# EthernetPhy.net
KiCad netlist of a schematic drawn in EAGLE
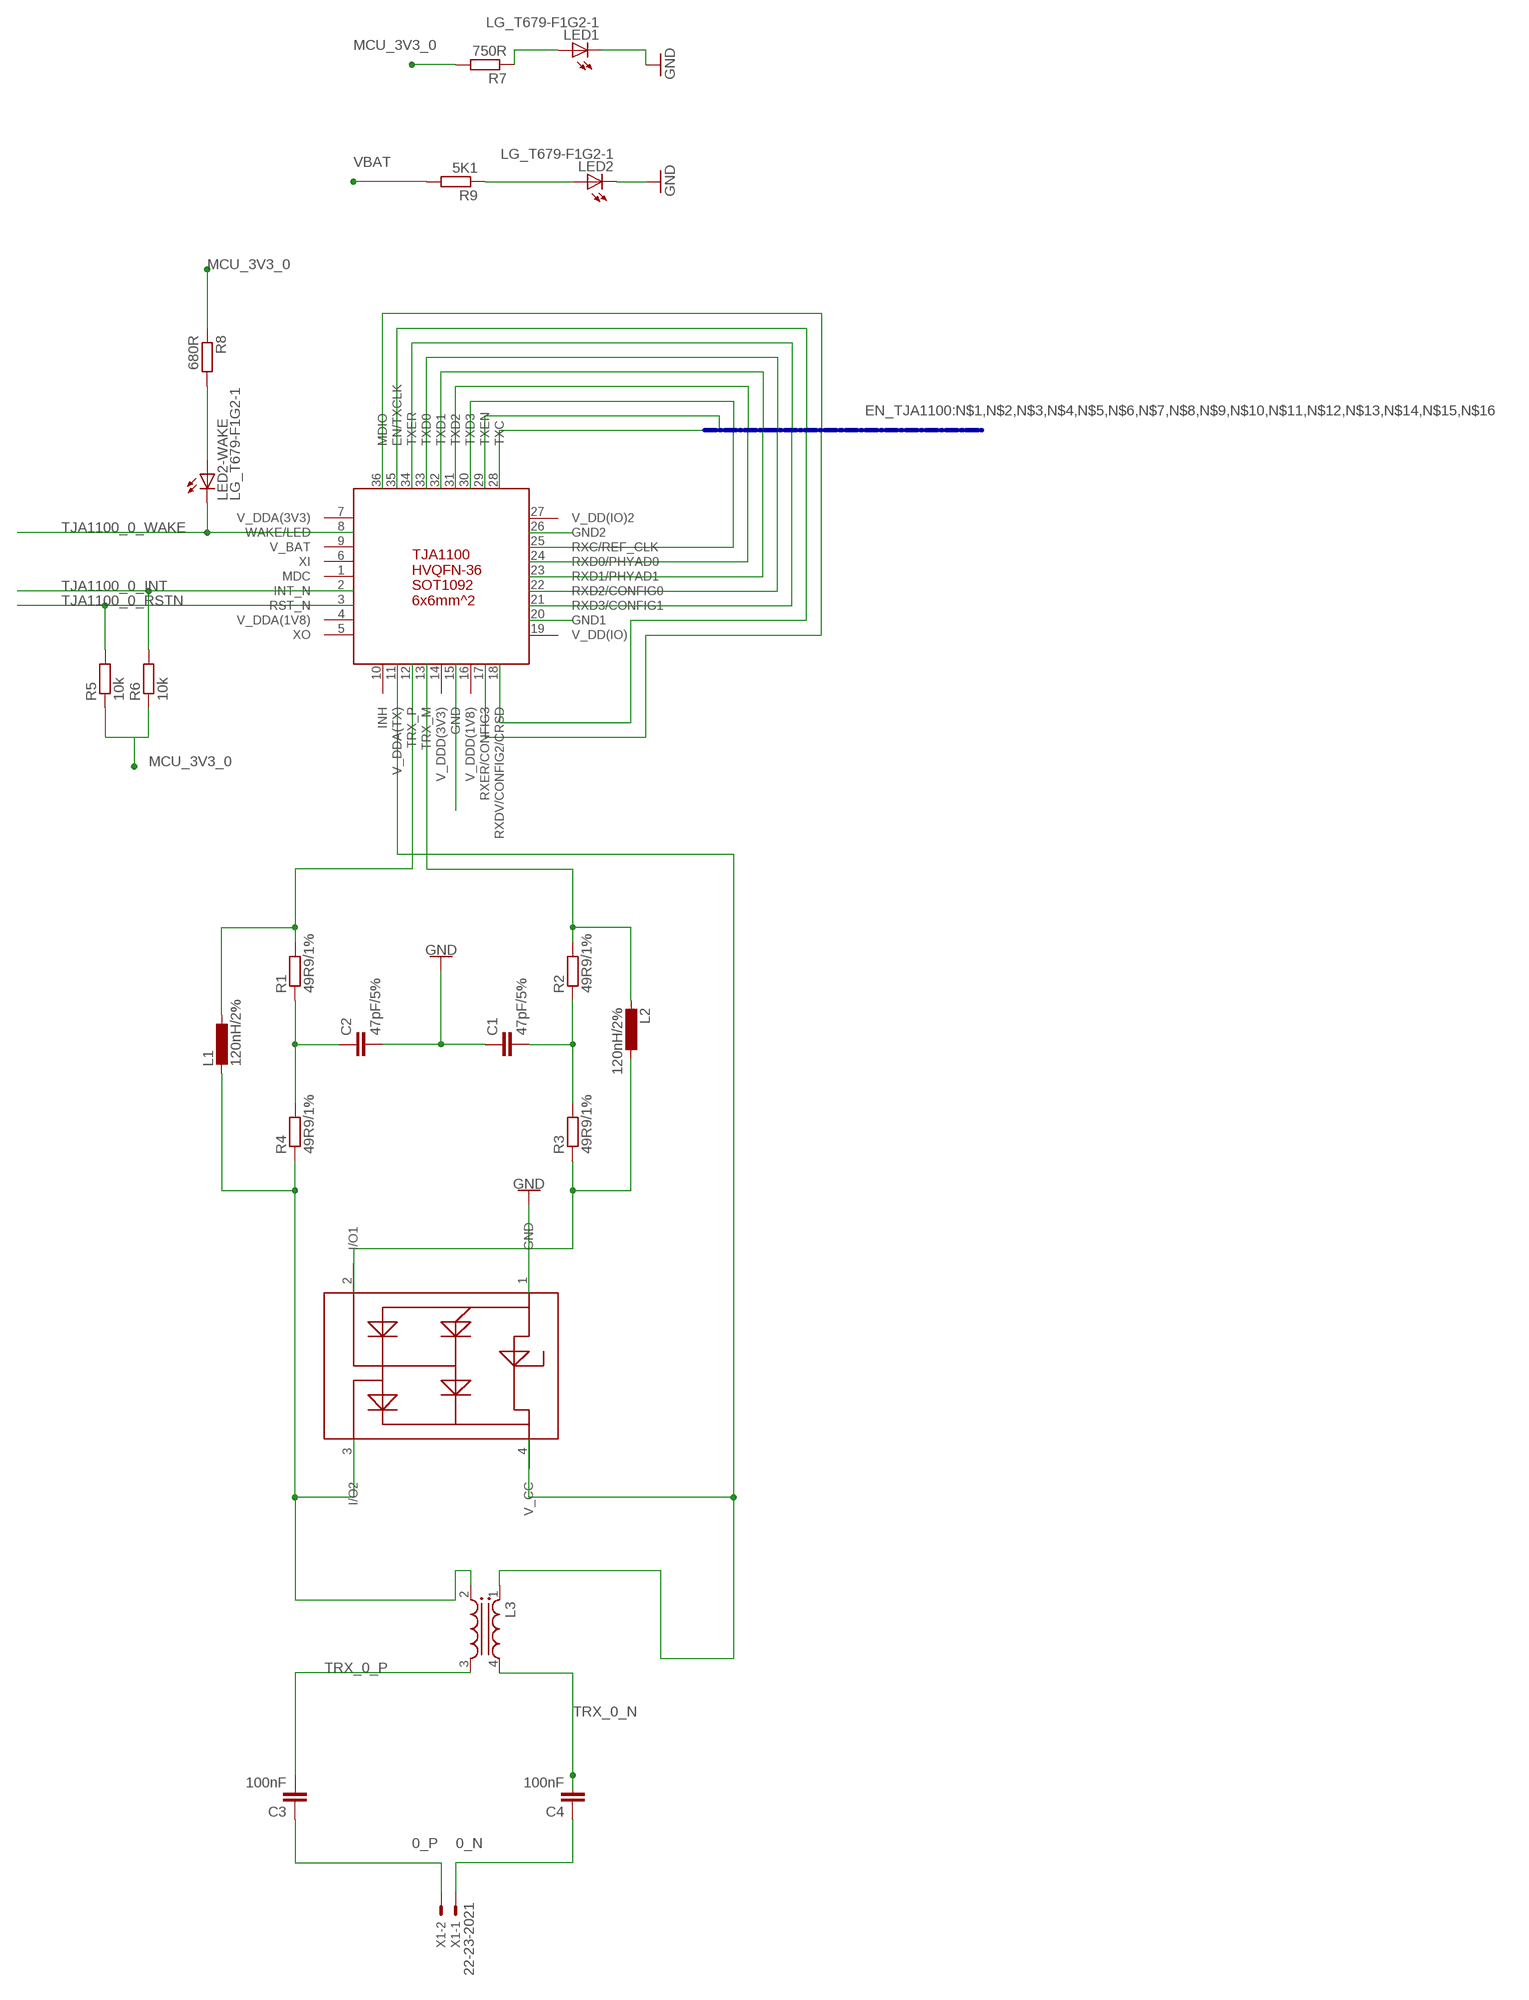
[diagram p0: schematic, sheet 1]

(export (version "E")
  (design (tool "Eeschema 10.0.6"))
  (components
    (comp (ref "C1")
      (value "47pF/5%")
      (footprint "eagle-import:C0402K")
      (libsource (lib "eagle-import") (part "C-EUC0402K"))
    )
    (comp (ref "C2")
      (value "47pF/5%")
      (footprint "eagle-import:C0402K")
      (libsource (lib "eagle-import") (part "C-EUC0402K"))
    )
    (comp (ref "C3")
      (value "100nF")
      (footprint "eagle-import:C0402K")
      (libsource (lib "eagle-import") (part "C-EUC0402K"))
    )
    (comp (ref "C4")
      (value "100nF")
      (footprint "eagle-import:C0402K")
      (libsource (lib "eagle-import") (part "C-EUC0402K"))
    )
    (comp (ref "L1")
      (value "120nH/2%")
      (footprint "eagle-import:L0201")
      (libsource (lib "eagle-import") (part "L-EUL0201"))
    )
    (comp (ref "L2")
      (value "120nH/2%")
      (footprint "eagle-import:L0201")
      (libsource (lib "eagle-import") (part "L-EUL0201"))
    )
    (comp (ref "L3")
      (value "WE-SL2_744224")
      (footprint "eagle-import:WE-SL2")
      (libsource (lib "eagle-import") (part "WE-SL2_744224"))
    )
    (comp (ref "LED1")
      (value "LG_T679-F1G2-1")
      (footprint "eagle-import:PLCC2")
      (libsource (lib "eagle-import") (part "_T679-?-1F1G2LG"))
    )
    (comp (ref "LED2")
      (value "LG_T679-F1G2-1")
      (footprint "eagle-import:PLCC2")
      (libsource (lib "eagle-import") (part "_T679-?-1F1G2LG"))
    )
    (comp (ref "LED2-WAKE")
      (value "LG_T679-F1G2-1")
      (footprint "eagle-import:PLCC2")
      (libsource (lib "eagle-import") (part "_T679-?-1F1G2LG"))
    )
    (comp (ref "R1")
      (value "49R9/1%")
      (footprint "eagle-import:MINI_MELF-0207R")
      (libsource (lib "eagle-import") (part "R-EU_MELF0207R"))
    )
    (comp (ref "R2")
      (value "49R9/1%")
      (footprint "eagle-import:MINI_MELF-0207R")
      (libsource (lib "eagle-import") (part "R-EU_MELF0207R"))
    )
    (comp (ref "R3")
      (value "49R9/1%")
      (footprint "eagle-import:MINI_MELF-0207R")
      (libsource (lib "eagle-import") (part "R-EU_MELF0207R"))
    )
    (comp (ref "R4")
      (value "49R9/1%")
      (footprint "eagle-import:MINI_MELF-0207R")
      (libsource (lib "eagle-import") (part "R-EU_MELF0207R"))
    )
    (comp (ref "R5")
      (value "10k")
      (footprint "eagle-import:R01005")
      (libsource (lib "eagle-import") (part "R-EU_01005"))
    )
    (comp (ref "R6")
      (value "10k")
      (footprint "eagle-import:R01005")
      (libsource (lib "eagle-import") (part "R-EU_01005"))
    )
    (comp (ref "R7")
      (value "750R")
      (footprint "eagle-import:R01005")
      (libsource (lib "eagle-import") (part "R-EU_01005"))
    )
    (comp (ref "R8")
      (value "680R")
      (footprint "eagle-import:R01005")
      (libsource (lib "eagle-import") (part "R-EU_01005"))
    )
    (comp (ref "R9")
      (value "5K1")
      (footprint "eagle-import:R01005")
      (libsource (lib "eagle-import") (part "R-EU_01005"))
    )
    (comp (ref "U$1")
      (value "TJA1100")
      (footprint "eagle-import:QFN50P605X605X100-36")
      (libsource (lib "eagle-import") (part "TJA1100"))
    )
    (comp (ref "U$2")
      (value "PESD2ETH-AX")
      (footprint "eagle-import:SOT192P237X114-4")
      (libsource (lib "eagle-import") (part "PESD2ETH-AX"))
    )
    (comp (ref "X1")
      (value "22-23-2021")
      (footprint "eagle-import:22-23-2021")
      (fields (field (name "MF") "MOLEX"))
      (libsource (lib "eagle-import") (part "22-23-2021"))
    )
  )
  (nets
    (net (code "17") (name "/0_N") (class "Default")
      (node (ref "C4") (pin "1") (pinfunction "1_1") (pintype "passive"))
      (node (ref "X1") (pin "1") (pinfunction "S_1") (pintype "passive"))
    )
    (net (code "18") (name "/0_P") (class "Default")
      (node (ref "C3") (pin "1") (pinfunction "1_1") (pintype "passive"))
      (node (ref "X1") (pin "2") (pinfunction "S_2") (pintype "passive"))
    )
    (net (code "19") (name "/MCU_3V3_0") (class "Default")
      (node (ref "R5") (pin "1") (pinfunction "1_1") (pintype "passive"))
      (node (ref "R6") (pin "1") (pinfunction "1_1") (pintype "passive"))
      (node (ref "R7") (pin "2") (pinfunction "2_2") (pintype "passive"))
      (node (ref "R8") (pin "1") (pinfunction "1_1") (pintype "passive"))
    )
    (net (code "20") (name "/TJA1100_0_INT") (class "Default")
      (node (ref "R6") (pin "2") (pinfunction "2_2") (pintype "passive"))
      (node (ref "U$1") (pin "2") (pinfunction "INT_N_2") (pintype "bidirectional"))
    )
    (net (code "21") (name "/TJA1100_0_RSTN") (class "Default")
      (node (ref "R5") (pin "2") (pinfunction "2_2") (pintype "passive"))
      (node (ref "U$1") (pin "3") (pinfunction "RST_N_3") (pintype "bidirectional"))
    )
    (net (code "22") (name "/TJA1100_0_WAKE") (class "Default")
      (node (ref "LED2-WAKE") (pin "C") (pinfunction "C_C") (pintype "passive"))
      (node (ref "U$1") (pin "8") (pinfunction "WAKE/LED_8") (pintype "bidirectional"))
    )
    (net (code "23") (name "/TRX_0_N") (class "Default")
      (node (ref "C4") (pin "2") (pinfunction "2_2") (pintype "passive"))
      (node (ref "L3") (pin "4") (pinfunction "2_4") (pintype "passive"))
    )
    (net (code "24") (name "/TRX_0_P") (class "Default")
      (node (ref "C3") (pin "2") (pinfunction "2_2") (pintype "passive"))
      (node (ref "L3") (pin "3") (pinfunction "3_3") (pintype "passive"))
    )
    (net (code "25") (name "/VBAT") (class "Default")
      (node (ref "R9") (pin "2") (pinfunction "2_2") (pintype "passive"))
    )
    (net (code "27") (name "GND") (class "Default")
      (node (ref "C1") (pin "1") (pinfunction "1_1") (pintype "passive"))
      (node (ref "C2") (pin "2") (pinfunction "2_2") (pintype "passive"))
      (node (ref "LED1") (pin "C") (pinfunction "C_C") (pintype "passive"))
      (node (ref "LED2") (pin "C") (pinfunction "C_C") (pintype "passive"))
      (node (ref "U$1") (pin "15") (pinfunction "GND_15") (pintype "bidirectional"))
      (node (ref "U$1") (pin "20") (pinfunction "GND1_20") (pintype "bidirectional"))
      (node (ref "U$1") (pin "26") (pinfunction "GND2_26") (pintype "bidirectional"))
      (node (ref "U$2") (pin "1") (pinfunction "GND_1") (pintype "bidirectional"))
    )
    (net (code "28") (name "Net-(C1-Pad2)") (class "Default")
      (node (ref "C1") (pin "2") (pinfunction "2_2") (pintype "passive"))
      (node (ref "R2") (pin "1") (pinfunction "1_1") (pintype "passive"))
      (node (ref "R3") (pin "2") (pinfunction "2_2") (pintype "passive"))
    )
    (net (code "29") (name "Net-(C2-Pad1)") (class "Default")
      (node (ref "C2") (pin "1") (pinfunction "1_1") (pintype "passive"))
      (node (ref "R1") (pin "1") (pinfunction "1_1") (pintype "passive"))
      (node (ref "R4") (pin "2") (pinfunction "2_2") (pintype "passive"))
    )
    (net (code "30") (name "Net-(L3-4)") (class "Default")
      (node (ref "L1") (pin "2") (pinfunction "2_2") (pintype "passive"))
      (node (ref "L3") (pin "2") (pinfunction "4_2") (pintype "passive"))
      (node (ref "R4") (pin "1") (pinfunction "1_1") (pintype "passive"))
      (node (ref "U$2") (pin "3") (pinfunction "I/O2_3") (pintype "bidirectional"))
    )
    (net (code "31") (name "Net-(LED1-PadA)") (class "Default")
      (node (ref "LED1") (pin "A") (pinfunction "A_A") (pintype "passive"))
      (node (ref "R7") (pin "1") (pinfunction "1_1") (pintype "passive"))
    )
    (net (code "32") (name "Net-(LED2-PadA)") (class "Default")
      (node (ref "LED2") (pin "A") (pinfunction "A_A") (pintype "passive"))
      (node (ref "R9") (pin "1") (pinfunction "1_1") (pintype "passive"))
    )
    (net (code "33") (name "Net-(LED2-WAKE-PadA)") (class "Default")
      (node (ref "LED2-WAKE") (pin "A") (pinfunction "A_A") (pintype "passive"))
      (node (ref "R8") (pin "2") (pinfunction "2_2") (pintype "passive"))
    )
    (net (code "34") (name "Net-(U$1-TRX_M)") (class "Default")
      (node (ref "L2") (pin "2") (pinfunction "2_2") (pintype "passive"))
      (node (ref "R2") (pin "2") (pinfunction "2_2") (pintype "passive"))
      (node (ref "U$1") (pin "13") (pinfunction "TRX_M_13") (pintype "bidirectional"))
    )
    (net (code "35") (name "Net-(U$1-TRX_P)") (class "Default")
      (node (ref "L1") (pin "1") (pinfunction "1_1") (pintype "passive"))
      (node (ref "R1") (pin "2") (pinfunction "2_2") (pintype "passive"))
      (node (ref "U$1") (pin "12") (pinfunction "TRX_P_12") (pintype "bidirectional"))
    )
    (net (code "36") (name "Net-(U$1-V_DDA(TX))") (class "Default")
      (node (ref "L3") (pin "1") (pinfunction "1_1") (pintype "passive"))
      (node (ref "U$1") (pin "11") (pinfunction "V_DDA(TX)_11") (pintype "bidirectional"))
      (node (ref "U$2") (pin "4") (pinfunction "V_CC_4") (pintype "bidirectional"))
    )
    (net (code "37") (name "Net-(U$2-I{slash}O1)") (class "Default")
      (node (ref "L2") (pin "1") (pinfunction "1_1") (pintype "passive"))
      (node (ref "R3") (pin "1") (pinfunction "1_1") (pintype "passive"))
      (node (ref "U$2") (pin "2") (pinfunction "I/O1_2") (pintype "bidirectional"))
    )
    (net (code "38") (name "unconnected-(U$1-EN{slash}TXCLK-Pad35)") (class "Default")
      (node (ref "U$1") (pin "35") (pinfunction "EN/TXCLK_35") (pintype "bidirectional"))
    )
    (net (code "39") (name "unconnected-(U$1-INH-Pad10)") (class "Default")
      (node (ref "U$1") (pin "10") (pinfunction "INH_10") (pintype "bidirectional"))
    )
    (net (code "40") (name "unconnected-(U$1-MDC-Pad1)") (class "Default")
      (node (ref "U$1") (pin "1") (pinfunction "MDC_1") (pintype "bidirectional"))
    )
    (net (code "41") (name "unconnected-(U$1-MDIO-Pad36)") (class "Default")
      (node (ref "U$1") (pin "36") (pinfunction "MDIO_36") (pintype "bidirectional"))
    )
    (net (code "42") (name "unconnected-(U$1-RXC{slash}REF_CLK-Pad25)") (class "Default")
      (node (ref "U$1") (pin "25") (pinfunction "RXC/REF_CLK_25") (pintype "bidirectional"))
    )
    (net (code "43") (name "unconnected-(U$1-RXD0{slash}PHYAD0-Pad24)") (class "Default")
      (node (ref "U$1") (pin "24") (pinfunction "RXD0/PHYAD0_24") (pintype "bidirectional"))
    )
    (net (code "44") (name "unconnected-(U$1-RXD1{slash}PHYAD1-Pad23)") (class "Default")
      (node (ref "U$1") (pin "23") (pinfunction "RXD1/PHYAD1_23") (pintype "bidirectional"))
    )
    (net (code "45") (name "unconnected-(U$1-RXD2{slash}CONFIG0-Pad22)") (class "Default")
      (node (ref "U$1") (pin "22") (pinfunction "RXD2/CONFIG0_22") (pintype "bidirectional"))
    )
    (net (code "46") (name "unconnected-(U$1-RXD3{slash}CONFIG1-Pad21)") (class "Default")
      (node (ref "U$1") (pin "21") (pinfunction "RXD3/CONFIG1_21") (pintype "bidirectional"))
    )
    (net (code "47") (name "unconnected-(U$1-RXDV{slash}CONFIG2{slash}CRSD-Pad18)") (class "Default")
      (node (ref "U$1") (pin "18") (pinfunction "RXDV/CONFIG2/CRSD_18") (pintype "bidirectional"))
    )
    (net (code "48") (name "unconnected-(U$1-RXER{slash}CONFIG3-Pad17)") (class "Default")
      (node (ref "U$1") (pin "17") (pinfunction "RXER/CONFIG3_17") (pintype "bidirectional"))
    )
    (net (code "49") (name "unconnected-(U$1-TXC-Pad28)") (class "Default")
      (node (ref "U$1") (pin "28") (pinfunction "TXC_28") (pintype "bidirectional"))
    )
    (net (code "50") (name "unconnected-(U$1-TXD0-Pad33)") (class "Default")
      (node (ref "U$1") (pin "33") (pinfunction "TXD0_33") (pintype "bidirectional"))
    )
    (net (code "51") (name "unconnected-(U$1-TXD1-Pad32)") (class "Default")
      (node (ref "U$1") (pin "32") (pinfunction "TXD1_32") (pintype "bidirectional"))
    )
    (net (code "52") (name "unconnected-(U$1-TXD2-Pad31)") (class "Default")
      (node (ref "U$1") (pin "31") (pinfunction "TXD2_31") (pintype "bidirectional"))
    )
    (net (code "53") (name "unconnected-(U$1-TXD3-Pad30)") (class "Default")
      (node (ref "U$1") (pin "30") (pinfunction "TXD3_30") (pintype "bidirectional"))
    )
    (net (code "54") (name "unconnected-(U$1-TXEN-Pad29)") (class "Default")
      (node (ref "U$1") (pin "29") (pinfunction "TXEN_29") (pintype "bidirectional"))
    )
    (net (code "55") (name "unconnected-(U$1-TXER-Pad34)") (class "Default")
      (node (ref "U$1") (pin "34") (pinfunction "TXER_34") (pintype "bidirectional"))
    )
    (net (code "56") (name "unconnected-(U$1-V_BAT-Pad9)") (class "Default")
      (node (ref "U$1") (pin "9") (pinfunction "V_BAT_9") (pintype "bidirectional"))
    )
    (net (code "57") (name "unconnected-(U$1-V_DD(IO)-Pad19)") (class "Default")
      (node (ref "U$1") (pin "19") (pinfunction "V_DD(IO)_19") (pintype "bidirectional"))
    )
    (net (code "58") (name "unconnected-(U$1-V_DD(IO)2-Pad27)") (class "Default")
      (node (ref "U$1") (pin "27") (pinfunction "V_DD(IO)2_27") (pintype "bidirectional"))
    )
    (net (code "59") (name "unconnected-(U$1-V_DDA(1V8)-Pad4)") (class "Default")
      (node (ref "U$1") (pin "4") (pinfunction "V_DDA(1V8)_4") (pintype "bidirectional"))
    )
    (net (code "60") (name "unconnected-(U$1-V_DDA(3V3)-Pad7)") (class "Default")
      (node (ref "U$1") (pin "7") (pinfunction "V_DDA(3V3)_7") (pintype "bidirectional"))
    )
    (net (code "61") (name "unconnected-(U$1-V_DDD(1V8)-Pad16)") (class "Default")
      (node (ref "U$1") (pin "16") (pinfunction "V_DDD(1V8)_16") (pintype "bidirectional"))
    )
    (net (code "62") (name "unconnected-(U$1-V_DDD(3V3)-Pad14)") (class "Default")
      (node (ref "U$1") (pin "14") (pinfunction "V_DDD(3V3)_14") (pintype "bidirectional"))
    )
    (net (code "63") (name "unconnected-(U$1-XI-Pad6)") (class "Default")
      (node (ref "U$1") (pin "6") (pinfunction "XI_6") (pintype "bidirectional"))
    )
    (net (code "64") (name "unconnected-(U$1-XO-Pad5)") (class "Default")
      (node (ref "U$1") (pin "5") (pinfunction "XO_5") (pintype "bidirectional"))
    )
  )
)
